# MASTER.net
KiCad netlist of a schematic drawn in Altium Designer
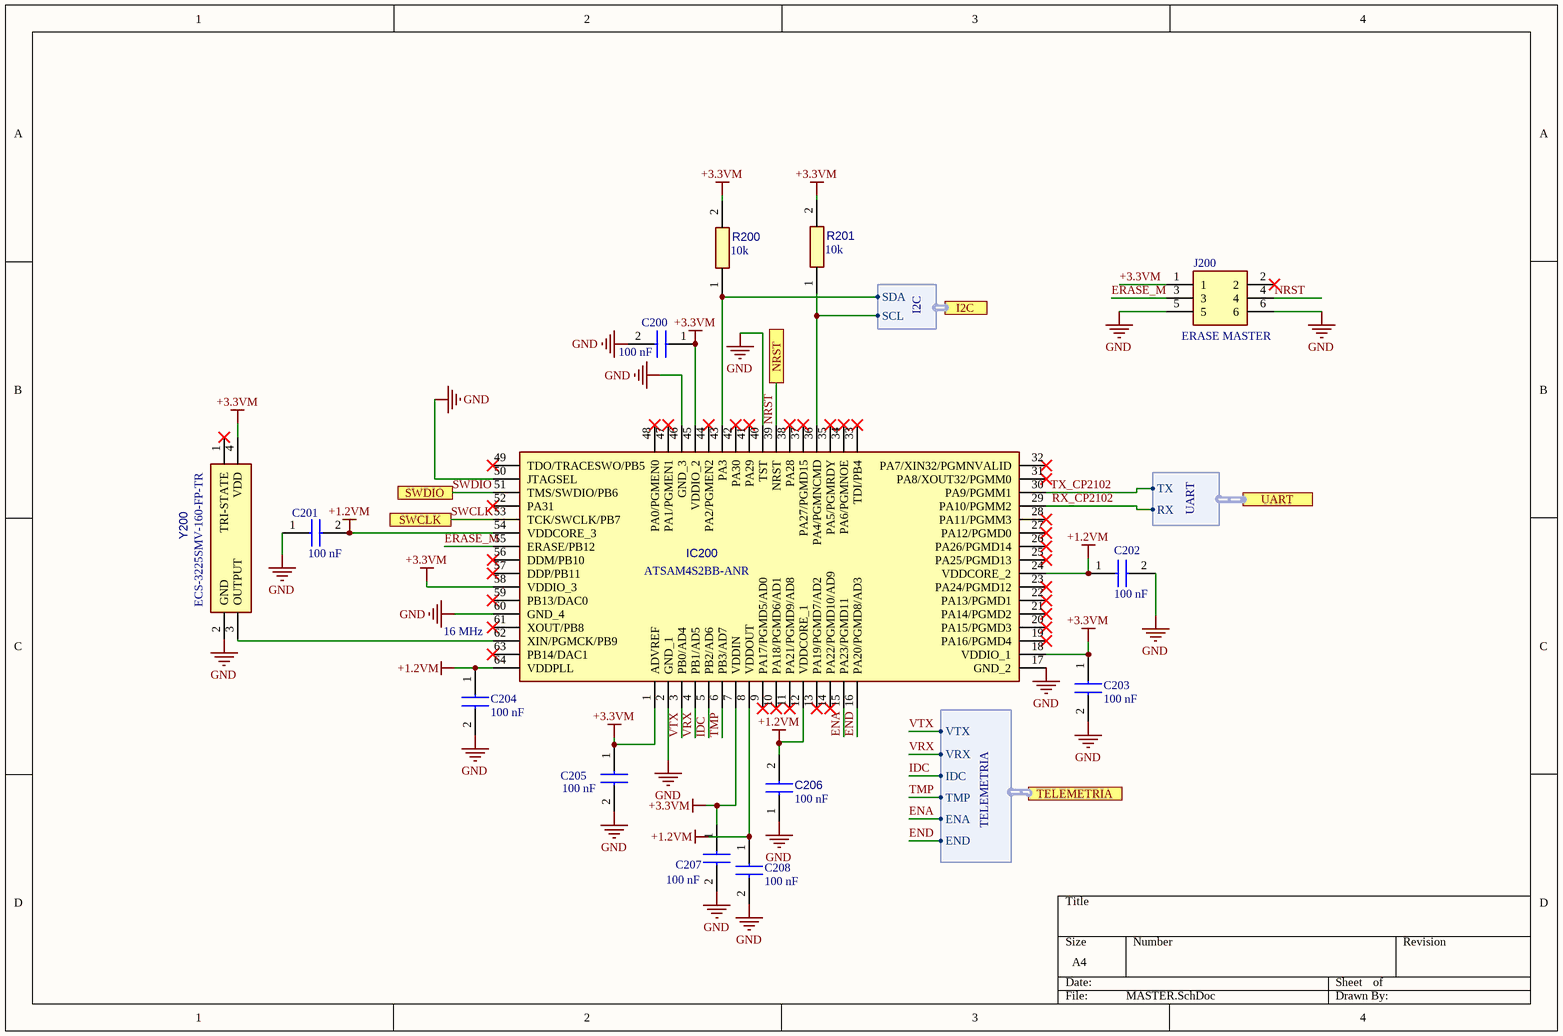
[diagram p0: MASTER.SchDoc]

(export (version "E")
  (design (tool "Eeschema 10.0.6"))
  (components
    (comp (ref "C200")
      (value "100 nF")
      (footprint "SamacSys:C0603")
      (description "Capacitor")
      (fields (field (name "MANUFACTURER_PART_NUMBER") "C0603H470J5GACTU"))
      (libsource (lib "LIBRERIA_GEN_V2.0") (part "C0603H470J5GACTU"))
    )
    (comp (ref "C201")
      (value "100 nF")
      (footprint "SamacSys:C0603")
      (description "Capacitor")
      (fields (field (name "MANUFACTURER_PART_NUMBER") "C0603H470J5GACTU"))
      (libsource (lib "LIBRERIA_GEN_V2.0") (part "C0603H470J5GACTU"))
    )
    (comp (ref "C202")
      (value "100 nF")
      (footprint "SamacSys:C0603")
      (description "Capacitor")
      (fields (field (name "MANUFACTURER_PART_NUMBER") "C0603H470J5GACTU"))
      (libsource (lib "LIBRERIA_GEN_V2.0") (part "C0603H470J5GACTU"))
    )
    (comp (ref "C203")
      (value "100 nF")
      (footprint "SamacSys:C0603")
      (description "Capacitor")
      (fields (field (name "MANUFACTURER_PART_NUMBER") "C0603H470J5GACTU"))
      (libsource (lib "LIBRERIA_GEN_V2.0") (part "C0603H470J5GACTU"))
    )
    (comp (ref "C204")
      (value "100 nF")
      (footprint "SamacSys:C0603")
      (description "Capacitor")
      (fields (field (name "MANUFACTURER_PART_NUMBER") "C0603H470J5GACTU"))
      (libsource (lib "LIBRERIA_GEN_V2.0") (part "C0603H470J5GACTU"))
    )
    (comp (ref "C205")
      (value "100 nF")
      (footprint "SamacSys:C0603")
      (description "Capacitor")
      (fields (field (name "MANUFACTURER_PART_NUMBER") "C0603H470J5GACTU"))
      (libsource (lib "LIBRERIA_GEN_V2.0") (part "C0603H470J5GACTU"))
    )
    (comp (ref "C206")
      (value "100 nF")
      (footprint "SamacSys:C0603")
      (description "Capacitor")
      (fields (field (name "MANUFACTURER_PART_NUMBER") "C0603H470J5GACTU"))
      (libsource (lib "*") (part "C0603H470J5GACTU"))
    )
    (comp (ref "C207")
      (value "100 nF")
      (footprint "SamacSys:C0603")
      (description "Capacitor")
      (fields (field (name "MANUFACTURER_PART_NUMBER") "C0603H470J5GACTU"))
      (libsource (lib "LIBRERIA_GEN_V2.0") (part "C0603H470J5GACTU"))
    )
    (comp (ref "C208")
      (value "100 nF")
      (footprint "SamacSys:C0603")
      (description "Capacitor")
      (fields (field (name "MANUFACTURER_PART_NUMBER") "C0603H470J5GACTU"))
      (libsource (lib "LIBRERIA_GEN_V2.0") (part "C0603H470J5GACTU"))
    )
    (comp (ref "IC200")
      (value "ATSAM4S2BB-ANR")
      (footprint "QFN50P905X905X75-65N:QFN50P905X905X75-65N")
      (description "Integrated Circuit")
      (fields (field (name "MOUSER PART NUMBER") "556-ATSAM4S2BB-ANR"))
      (libsource (lib "*") (part "ATSAM4S2BB-ANR"))
    )
    (comp (ref "J200")
      (value "ERASE MASTER")
      (footprint "SamacSys:HDRV6W64P254_2X3_762X508X889P")
      (description "Connector")
      (fields
        (field (name "MANUFACTURER_PART_NUMBER") "61300621121")
        (field (name "MOUSER PART NUMBER") "710-61300621121")
      )
      (libsource (lib "*") (part "61300621121"))
    )
    (comp (ref "R200")
      (value "10k")
      (footprint "SamacSys:RESC1608X55N")
      (description "Resistor")
      (fields
        (field (name "MANUFACTURER_PART_NUMBER") "CR0603-FX-1431ELF")
        (field (name "MOUSER PART NUMBER") "652-CR0603FX-1431ELF")
      )
      (libsource (lib "*") (part "CR0603-FX-1431ELF"))
    )
    (comp (ref "R201")
      (value "10k")
      (footprint "SamacSys:RESC1608X55N")
      (description "Resistor")
      (fields
        (field (name "MANUFACTURER_PART_NUMBER") "CR0603-FX-1431ELF")
        (field (name "MOUSER PART NUMBER") "652-CR0603FX-1431ELF")
      )
      (libsource (lib "*") (part "CR0603-FX-1431ELF"))
    )
    (comp (ref "Y200")
      (value "ECS-3225SMV-160-FP-TR")
      (footprint "SamacSys:ECS3225SMV160FPTR")
      (description "Crystal or Oscillator")
      (fields (field (name "MOUSER PART NUMBER") "520-3225SMV-160-FPT"))
      (libsource (lib "*") (part "ECS-3225SMV-160-FP-TR"))
    )
  )
  (nets
    (net (code "4") (name "+1.2VM") (class "Default")
      (node (ref "C201") (pin "2") (pinfunction "2_2") (pintype "passive"))
      (node (ref "C202") (pin "1") (pinfunction "1_1") (pintype "passive"))
      (node (ref "C204") (pin "1") (pinfunction "1_1") (pintype "passive"))
      (node (ref "C206") (pin "2") (pinfunction "2_2") (pintype "passive"))
      (node (ref "C208") (pin "1") (pinfunction "1_1") (pintype "passive"))
      (node (ref "IC200") (pin "12") (pinfunction "VDDCORE_1_12") (pintype "passive"))
      (node (ref "IC200") (pin "24") (pinfunction "VDDCORE_2_24") (pintype "passive"))
      (node (ref "IC200") (pin "54") (pinfunction "VDDCORE_3_54") (pintype "passive"))
      (node (ref "IC200") (pin "64") (pinfunction "VDDPLL_64") (pintype "passive"))
      (node (ref "IC200") (pin "8") (pinfunction "VDDOUT_8") (pintype "passive"))
    )
    (net (code "5") (name "+3.3VM") (class "Default")
      (node (ref "C200") (pin "1") (pinfunction "1_1") (pintype "passive"))
      (node (ref "C203") (pin "1") (pinfunction "1_1") (pintype "passive"))
      (node (ref "C205") (pin "1") (pinfunction "1_1") (pintype "passive"))
      (node (ref "C207") (pin "1") (pinfunction "1_1") (pintype "passive"))
      (node (ref "IC200") (pin "1") (pinfunction "ADVREF_1") (pintype "passive"))
      (node (ref "IC200") (pin "18") (pinfunction "VDDIO_1_18") (pintype "passive"))
      (node (ref "IC200") (pin "45") (pinfunction "VDDIO_2_45") (pintype "passive"))
      (node (ref "IC200") (pin "58") (pinfunction "VDDIO_3_58") (pintype "passive"))
      (node (ref "IC200") (pin "7") (pinfunction "VDDIN_7") (pintype "passive"))
      (node (ref "J200") (pin "1") (pinfunction "1_1") (pintype "passive"))
      (node (ref "R200") (pin "2") (pinfunction "2_2") (pintype "passive"))
      (node (ref "R201") (pin "2") (pinfunction "2_2") (pintype "passive"))
      (node (ref "Y200") (pin "4") (pinfunction "VDD_4") (pintype "passive"))
    )
    (net (code "6") (name "/ENA") (class "Default")
      (node (ref "IC200") (pin "15") (pinfunction "PA23/PGMD11_15") (pintype "passive"))
    )
    (net (code "7") (name "/END") (class "Default")
      (node (ref "IC200") (pin "16") (pinfunction "PA20/PGMD8/AD3_16") (pintype "passive"))
    )
    (net (code "8") (name "/ERASE_M") (class "Default")
      (node (ref "IC200") (pin "55") (pinfunction "ERASE/PB12_55") (pintype "passive"))
      (node (ref "J200") (pin "3") (pinfunction "3_3") (pintype "passive"))
    )
    (net (code "9") (name "/IDC") (class "Default")
      (node (ref "IC200") (pin "5") (pinfunction "PB2/AD6_5") (pintype "passive"))
    )
    (net (code "10") (name "/NRST") (class "Default")
      (node (ref "IC200") (pin "39") (pinfunction "NRST_39") (pintype "passive"))
      (node (ref "J200") (pin "4") (pinfunction "4_4") (pintype "passive"))
    )
    (net (code "11") (name "/RX_CP2102") (class "Default")
      (node (ref "IC200") (pin "29") (pinfunction "PA10/PGMM2_29") (pintype "passive"))
    )
    (net (code "12") (name "/SWCLK") (class "Default")
      (node (ref "IC200") (pin "53") (pinfunction "TCK/SWCLK/PB7_53") (pintype "passive"))
    )
    (net (code "13") (name "/SWDIO") (class "Default")
      (node (ref "IC200") (pin "51") (pinfunction "TMS/SWDIO/PB6_51") (pintype "passive"))
    )
    (net (code "14") (name "/TMP") (class "Default")
      (node (ref "IC200") (pin "6") (pinfunction "PB3/AD7_6") (pintype "passive"))
    )
    (net (code "15") (name "/TX_CP2102") (class "Default")
      (node (ref "IC200") (pin "30") (pinfunction "PA9/PGMM1_30") (pintype "passive"))
    )
    (net (code "16") (name "/VRX") (class "Default")
      (node (ref "IC200") (pin "4") (pinfunction "PB1/AD5_4") (pintype "passive"))
    )
    (net (code "17") (name "/VTX") (class "Default")
      (node (ref "IC200") (pin "3") (pinfunction "PB0/AD4_3") (pintype "passive"))
    )
    (net (code "21") (name "GND") (class "Default")
      (node (ref "C200") (pin "2") (pinfunction "2_2") (pintype "passive"))
      (node (ref "C201") (pin "1") (pinfunction "1_1") (pintype "passive"))
      (node (ref "C202") (pin "2") (pinfunction "2_2") (pintype "passive"))
      (node (ref "C203") (pin "2") (pinfunction "2_2") (pintype "passive"))
      (node (ref "C204") (pin "2") (pinfunction "2_2") (pintype "passive"))
      (node (ref "C205") (pin "2") (pinfunction "2_2") (pintype "passive"))
      (node (ref "C206") (pin "1") (pinfunction "1_1") (pintype "passive"))
      (node (ref "C207") (pin "2") (pinfunction "2_2") (pintype "passive"))
      (node (ref "C208") (pin "2") (pinfunction "2_2") (pintype "passive"))
      (node (ref "IC200") (pin "17") (pinfunction "GND_2_17") (pintype "passive"))
      (node (ref "IC200") (pin "2") (pinfunction "GND_1_2") (pintype "passive"))
      (node (ref "IC200") (pin "40") (pinfunction "TST_40") (pintype "passive"))
      (node (ref "IC200") (pin "46") (pinfunction "GND_3_46") (pintype "passive"))
      (node (ref "IC200") (pin "50") (pinfunction "JTAGSEL_50") (pintype "passive"))
      (node (ref "IC200") (pin "60") (pinfunction "GND_4_60") (pintype "passive"))
      (node (ref "J200") (pin "5") (pinfunction "5_5") (pintype "passive"))
      (node (ref "J200") (pin "6") (pinfunction "6_6") (pintype "passive"))
      (node (ref "Y200") (pin "2") (pinfunction "GND_2") (pintype "passive"))
    )
    (net (code "22") (name "Net-(IC200-PA3)") (class "Default")
      (node (ref "IC200") (pin "43") (pinfunction "PA3_43") (pintype "passive"))
      (node (ref "R200") (pin "1") (pinfunction "1_1") (pintype "passive"))
    )
    (net (code "23") (name "Net-(IC200-PA4{slash}PGMNCMD)") (class "Default")
      (node (ref "IC200") (pin "36") (pinfunction "PA4/PGMNCMD_36") (pintype "passive"))
      (node (ref "R201") (pin "1") (pinfunction "1_1") (pintype "passive"))
    )
    (net (code "24") (name "Net-(IC200-XIN{slash}PGMCK{slash}PB9)") (class "Default")
      (node (ref "IC200") (pin "62") (pinfunction "XIN/PGMCK/PB9_62") (pintype "passive"))
      (node (ref "Y200") (pin "3") (pinfunction "OUTPUT_3") (pintype "passive"))
    )
    (net (code "25") (name "unconnected-(IC200-DDM{slash}PB10-Pad56)") (class "Default")
      (node (ref "IC200") (pin "56") (pinfunction "DDM/PB10_56") (pintype "passive+no_connect"))
    )
    (net (code "26") (name "unconnected-(IC200-DDP{slash}PB11-Pad57)") (class "Default")
      (node (ref "IC200") (pin "57") (pinfunction "DDP/PB11_57") (pintype "passive+no_connect"))
    )
    (net (code "27") (name "unconnected-(IC200-PA0{slash}PGMEN0-Pad48)") (class "Default")
      (node (ref "IC200") (pin "48") (pinfunction "PA0/PGMEN0_48") (pintype "passive+no_connect"))
    )
    (net (code "28") (name "unconnected-(IC200-PA1{slash}PGMEN1-Pad47)") (class "Default")
      (node (ref "IC200") (pin "47") (pinfunction "PA1/PGMEN1_47") (pintype "passive+no_connect"))
    )
    (net (code "29") (name "unconnected-(IC200-PA2{slash}PGMEN2-Pad44)") (class "Default")
      (node (ref "IC200") (pin "44") (pinfunction "PA2/PGMEN2_44") (pintype "passive+no_connect"))
    )
    (net (code "30") (name "unconnected-(IC200-PA5{slash}PGMRDY-Pad35)") (class "Default")
      (node (ref "IC200") (pin "35") (pinfunction "PA5/PGMRDY_35") (pintype "passive+no_connect"))
    )
    (net (code "31") (name "unconnected-(IC200-PA6{slash}PGMNOE-Pad34)") (class "Default")
      (node (ref "IC200") (pin "34") (pinfunction "PA6/PGMNOE_34") (pintype "passive+no_connect"))
    )
    (net (code "32") (name "unconnected-(IC200-PA7{slash}XIN32{slash}PGMNVALID-Pad32)") (class "Default")
      (node (ref "IC200") (pin "32") (pinfunction "PA7/XIN32/PGMNVALID_32") (pintype "passive+no_connect"))
    )
    (net (code "33") (name "unconnected-(IC200-PA8{slash}XOUT32{slash}PGMM0-Pad31)") (class "Default")
      (node (ref "IC200") (pin "31") (pinfunction "PA8/XOUT32/PGMM0_31") (pintype "passive+no_connect"))
    )
    (net (code "34") (name "unconnected-(IC200-PA11{slash}PGMM3-Pad28)") (class "Default")
      (node (ref "IC200") (pin "28") (pinfunction "PA11/PGMM3_28") (pintype "passive+no_connect"))
    )
    (net (code "35") (name "unconnected-(IC200-PA12{slash}PGMD0-Pad27)") (class "Default")
      (node (ref "IC200") (pin "27") (pinfunction "PA12/PGMD0_27") (pintype "passive+no_connect"))
    )
    (net (code "36") (name "unconnected-(IC200-PA13{slash}PGMD1-Pad22)") (class "Default")
      (node (ref "IC200") (pin "22") (pinfunction "PA13/PGMD1_22") (pintype "passive+no_connect"))
    )
    (net (code "37") (name "unconnected-(IC200-PA14{slash}PGMD2-Pad21)") (class "Default")
      (node (ref "IC200") (pin "21") (pinfunction "PA14/PGMD2_21") (pintype "passive+no_connect"))
    )
    (net (code "38") (name "unconnected-(IC200-PA15{slash}PGMD3-Pad20)") (class "Default")
      (node (ref "IC200") (pin "20") (pinfunction "PA15/PGMD3_20") (pintype "passive+no_connect"))
    )
    (net (code "39") (name "unconnected-(IC200-PA16{slash}PGMD4-Pad19)") (class "Default")
      (node (ref "IC200") (pin "19") (pinfunction "PA16/PGMD4_19") (pintype "passive+no_connect"))
    )
    (net (code "40") (name "unconnected-(IC200-PA17{slash}PGMD5{slash}AD0-Pad9)") (class "Default")
      (node (ref "IC200") (pin "9") (pinfunction "PA17/PGMD5/AD0_9") (pintype "passive+no_connect"))
    )
    (net (code "41") (name "unconnected-(IC200-PA18{slash}PGMD6{slash}AD1-Pad10)") (class "Default")
      (node (ref "IC200") (pin "10") (pinfunction "PA18/PGMD6/AD1_10") (pintype "passive+no_connect"))
    )
    (net (code "42") (name "unconnected-(IC200-PA19{slash}PGMD7{slash}AD2-Pad13)") (class "Default")
      (node (ref "IC200") (pin "13") (pinfunction "PA19/PGMD7/AD2_13") (pintype "passive+no_connect"))
    )
    (net (code "43") (name "unconnected-(IC200-PA21{slash}PGMD9{slash}AD8-Pad11)") (class "Default")
      (node (ref "IC200") (pin "11") (pinfunction "PA21/PGMD9/AD8_11") (pintype "passive+no_connect"))
    )
    (net (code "44") (name "unconnected-(IC200-PA22{slash}PGMD10{slash}AD9-Pad14)") (class "Default")
      (node (ref "IC200") (pin "14") (pinfunction "PA22/PGMD10/AD9_14") (pintype "passive+no_connect"))
    )
    (net (code "45") (name "unconnected-(IC200-PA24{slash}PGMD12-Pad23)") (class "Default")
      (node (ref "IC200") (pin "23") (pinfunction "PA24/PGMD12_23") (pintype "passive+no_connect"))
    )
    (net (code "46") (name "unconnected-(IC200-PA25{slash}PGMD13-Pad25)") (class "Default")
      (node (ref "IC200") (pin "25") (pinfunction "PA25/PGMD13_25") (pintype "passive+no_connect"))
    )
    (net (code "47") (name "unconnected-(IC200-PA26{slash}PGMD14-Pad26)") (class "Default")
      (node (ref "IC200") (pin "26") (pinfunction "PA26/PGMD14_26") (pintype "passive+no_connect"))
    )
    (net (code "48") (name "unconnected-(IC200-PA27{slash}PGMD15-Pad37)") (class "Default")
      (node (ref "IC200") (pin "37") (pinfunction "PA27/PGMD15_37") (pintype "passive+no_connect"))
    )
    (net (code "49") (name "unconnected-(IC200-PA28-Pad38)") (class "Default")
      (node (ref "IC200") (pin "38") (pinfunction "PA28_38") (pintype "passive+no_connect"))
    )
    (net (code "50") (name "unconnected-(IC200-PA29-Pad41)") (class "Default")
      (node (ref "IC200") (pin "41") (pinfunction "PA29_41") (pintype "passive+no_connect"))
    )
    (net (code "51") (name "unconnected-(IC200-PA30-Pad42)") (class "Default")
      (node (ref "IC200") (pin "42") (pinfunction "PA30_42") (pintype "passive+no_connect"))
    )
    (net (code "52") (name "unconnected-(IC200-PA31-Pad52)") (class "Default")
      (node (ref "IC200") (pin "52") (pinfunction "PA31_52") (pintype "passive+no_connect"))
    )
    (net (code "53") (name "unconnected-(IC200-PB13{slash}DAC0-Pad59)") (class "Default")
      (node (ref "IC200") (pin "59") (pinfunction "PB13/DAC0_59") (pintype "passive+no_connect"))
    )
    (net (code "54") (name "unconnected-(IC200-PB14{slash}DAC1-Pad63)") (class "Default")
      (node (ref "IC200") (pin "63") (pinfunction "PB14/DAC1_63") (pintype "passive+no_connect"))
    )
    (net (code "55") (name "unconnected-(IC200-TDI{slash}PB4-Pad33)") (class "Default")
      (node (ref "IC200") (pin "33") (pinfunction "TDI/PB4_33") (pintype "passive+no_connect"))
    )
    (net (code "56") (name "unconnected-(IC200-TDO{slash}TRACESWO{slash}PB5-Pad49)") (class "Default")
      (node (ref "IC200") (pin "49") (pinfunction "TDO/TRACESWO/PB5_49") (pintype "passive+no_connect"))
    )
    (net (code "57") (name "unconnected-(IC200-XOUT{slash}PB8-Pad61)") (class "Default")
      (node (ref "IC200") (pin "61") (pinfunction "XOUT/PB8_61") (pintype "passive+no_connect"))
    )
    (net (code "58") (name "unconnected-(J200-Pad2)") (class "Default")
      (node (ref "J200") (pin "2") (pinfunction "2_2") (pintype "passive+no_connect"))
    )
    (net (code "59") (name "unconnected-(Y200-TRI-STATE-Pad1)") (class "Default")
      (node (ref "Y200") (pin "1") (pinfunction "TRI-STATE_1") (pintype "passive+no_connect"))
    )
  )
)
